# ESP-01S-WS-V1_0.net
KiCad netlist of a schematic drawn in Altium Designer
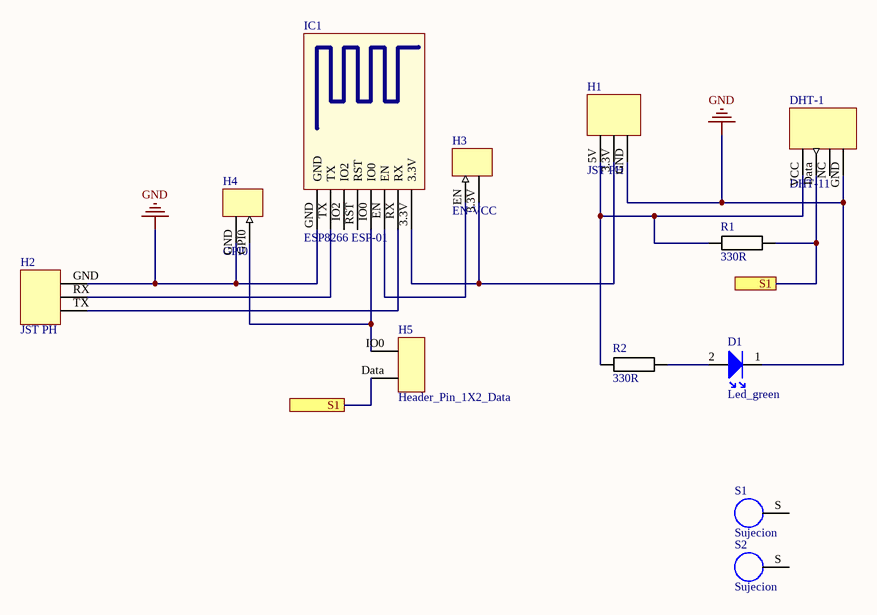
[diagram p0: ESP-01S-WS-V1.0.SchDoc]

(export (version "E")
  (design (tool "Eeschema 10.0.6"))
  (components
    (comp (ref "D1")
      (value "Led_green")
      (footprint "Diode_5mm_green")
      (libsource (lib "Schlib-PCB-Invernadero") (part "Led_green"))
    )
    (comp (ref "DHT-1")
      (value "DHT-11")
      (footprint "DHT-11")
      (libsource (lib "Schlib-ESP-01S-WS-V1.0") (part "DHT-11"))
    )
    (comp (ref "H1")
      (value "JST PH")
      (footprint "JST-PH-VCC")
      (libsource (lib "Schlib-ESP-01S-WS-V1.0") (part "Header_Pin_1X3_VCC"))
    )
    (comp (ref "H2")
      (value "JST PH")
      (footprint "HEADER_PIN_1X3_SERIAL")
      (libsource (lib "Schlib-ESP-01S-WS-V1.0") (part "Header_Pin_1X3_SERIAL"))
    )
    (comp (ref "H3")
      (value "EN-VCC")
      (footprint "Header_Pin_1X2-EN")
      (libsource (lib "Schlib-ESP-01S-WS-V1.0") (part "Header_Pin_1X2_EN"))
    )
    (comp (ref "H4")
      (value "GPI0")
      (footprint "Header_Pin_1X2-GPI0")
      (libsource (lib "Schlib-ESP-01S-WS-V1.0") (part "Header_Pin_1X2_GPI0"))
    )
    (comp (ref "H5")
      (value "Header_Pin_1X2_Data")
      (footprint "Header_Pin_1X2_Data")
      (libsource (lib "Schlib-ESP-01S-WS-V1.0") (part "Header_Pin_1X2_Data"))
    )
    (comp (ref "IC1")
      (value "ESP8266 ESP-01")
      (footprint "ESP8266 ESP-01")
      (libsource (lib "ESP8266") (part "ESP8266 ESP-01"))
    )
    (comp (ref "R1")
      (value "330R")
      (footprint "330R_P8mm_0.25W")
      (libsource (lib "Schlib-PCB-Invernadero") (part "330R_0.25W"))
    )
    (comp (ref "R2")
      (value "330R")
      (footprint "330R_P8mm_0.25W")
      (libsource (lib "Schlib-PCB-Invernadero") (part "330R_0.25W"))
    )
    (comp (ref "S1")
      (value "Sujecion")
      (footprint "SUJECION")
      (libsource (lib "Schlib-ESP-01S-WS-V1.0") (part "SUJECION"))
    )
    (comp (ref "S2")
      (value "Sujecion")
      (footprint "SUJECION")
      (libsource (lib "Schlib-ESP-01S-WS-V1.0") (part "SUJECION"))
    )
  )
  (nets
    (net (code "1") (name "/S1") (class "Default")
      (node (ref "DHT-1") (pin "Data") (pinfunction "Data_Data") (pintype "output"))
      (node (ref "H5") (pin "Data") (pinfunction "Data_Data") (pintype "passive"))
      (node (ref "R1") (pin "2") (pinfunction "2_2") (pintype "passive"))
    )
    (net (code "2") (name "GND") (class "Default")
      (node (ref "D1") (pin "1") (pinfunction "1_1") (pintype "passive"))
      (node (ref "DHT-1") (pin "GND") (pinfunction "GND_GND") (pintype "passive"))
      (node (ref "H1") (pin "GND") (pinfunction "GND_GND") (pintype "passive"))
      (node (ref "H2") (pin "GND") (pinfunction "GND_GND") (pintype "passive"))
      (node (ref "H4") (pin "GND") (pinfunction "GND_GND") (pintype "passive"))
      (node (ref "IC1") (pin "GND") (pinfunction "GND_GND") (pintype "passive"))
    )
    (net (code "3") (name "Net-(D1-Pad2)") (class "Default")
      (node (ref "D1") (pin "2") (pinfunction "2_2") (pintype "passive"))
      (node (ref "R2") (pin "2") (pinfunction "2_2") (pintype "passive"))
    )
    (net (code "4") (name "Net-(DHT-1-PadVCC)") (class "Default")
      (node (ref "DHT-1") (pin "VCC") (pinfunction "VCC_VCC") (pintype "power_in"))
      (node (ref "H1") (pin "5V") (pinfunction "5V_5V") (pintype "passive"))
      (node (ref "R1") (pin "1") (pinfunction "1_1") (pintype "passive"))
      (node (ref "R2") (pin "1") (pinfunction "1_1") (pintype "passive"))
    )
    (net (code "5") (name "Net-(H1-Pad3.3V)") (class "Default")
      (node (ref "H1") (pin "3.3V") (pinfunction "3.3V_3.3V") (pintype "passive"))
      (node (ref "H3") (pin "3.3V") (pinfunction "3.3V_3.3V") (pintype "passive"))
      (node (ref "IC1") (pin "3.3V") (pinfunction "3.3V_3.3V") (pintype "passive"))
    )
    (net (code "6") (name "Net-(H2-PadRX)") (class "Default")
      (node (ref "H2") (pin "RX") (pinfunction "RX_RX") (pintype "passive"))
      (node (ref "IC1") (pin "TX") (pinfunction "TX_TX") (pintype "passive"))
    )
    (net (code "7") (name "Net-(H2-PadTX)") (class "Default")
      (node (ref "H2") (pin "TX") (pinfunction "TX_TX") (pintype "passive"))
      (node (ref "IC1") (pin "RX") (pinfunction "RX_RX") (pintype "passive"))
    )
    (net (code "8") (name "Net-(H3-PadEN)") (class "Default")
      (node (ref "H3") (pin "EN") (pinfunction "EN_EN") (pintype "input"))
      (node (ref "IC1") (pin "EN") (pinfunction "EN_EN") (pintype "passive"))
    )
    (net (code "9") (name "Net-(H4-PadGPI0)") (class "Default")
      (node (ref "H4") (pin "GPI0") (pinfunction "GPI0_GPI0") (pintype "input"))
      (node (ref "H5") (pin "IO0") (pinfunction "IO0_IO0") (pintype "passive"))
      (node (ref "IC1") (pin "IO0") (pinfunction "IO0_IO0") (pintype "passive"))
    )
    (net (code "10") (name "unconnected-(DHT-1-PadNC)") (class "Default")
      (node (ref "DHT-1") (pin "NC") (pinfunction "NC_NC") (pintype "passive"))
    )
    (net (code "11") (name "unconnected-(IC1-PadIO2)") (class "Default")
      (node (ref "IC1") (pin "IO2") (pinfunction "IO2_IO2") (pintype "passive"))
    )
    (net (code "12") (name "unconnected-(IC1-PadRST)") (class "Default")
      (node (ref "IC1") (pin "RST") (pinfunction "RST_RST") (pintype "passive"))
    )
    (net (code "13") (name "unconnected-(S1-PadS)") (class "Default")
      (node (ref "S1") (pin "S") (pinfunction "S_S") (pintype "passive"))
    )
    (net (code "14") (name "unconnected-(S2-PadS)") (class "Default")
      (node (ref "S2") (pin "S") (pinfunction "S_S") (pintype "passive"))
    )
  )
)
